# Receptor_RF.net
KiCad netlist of a schematic drawn in EAGLE
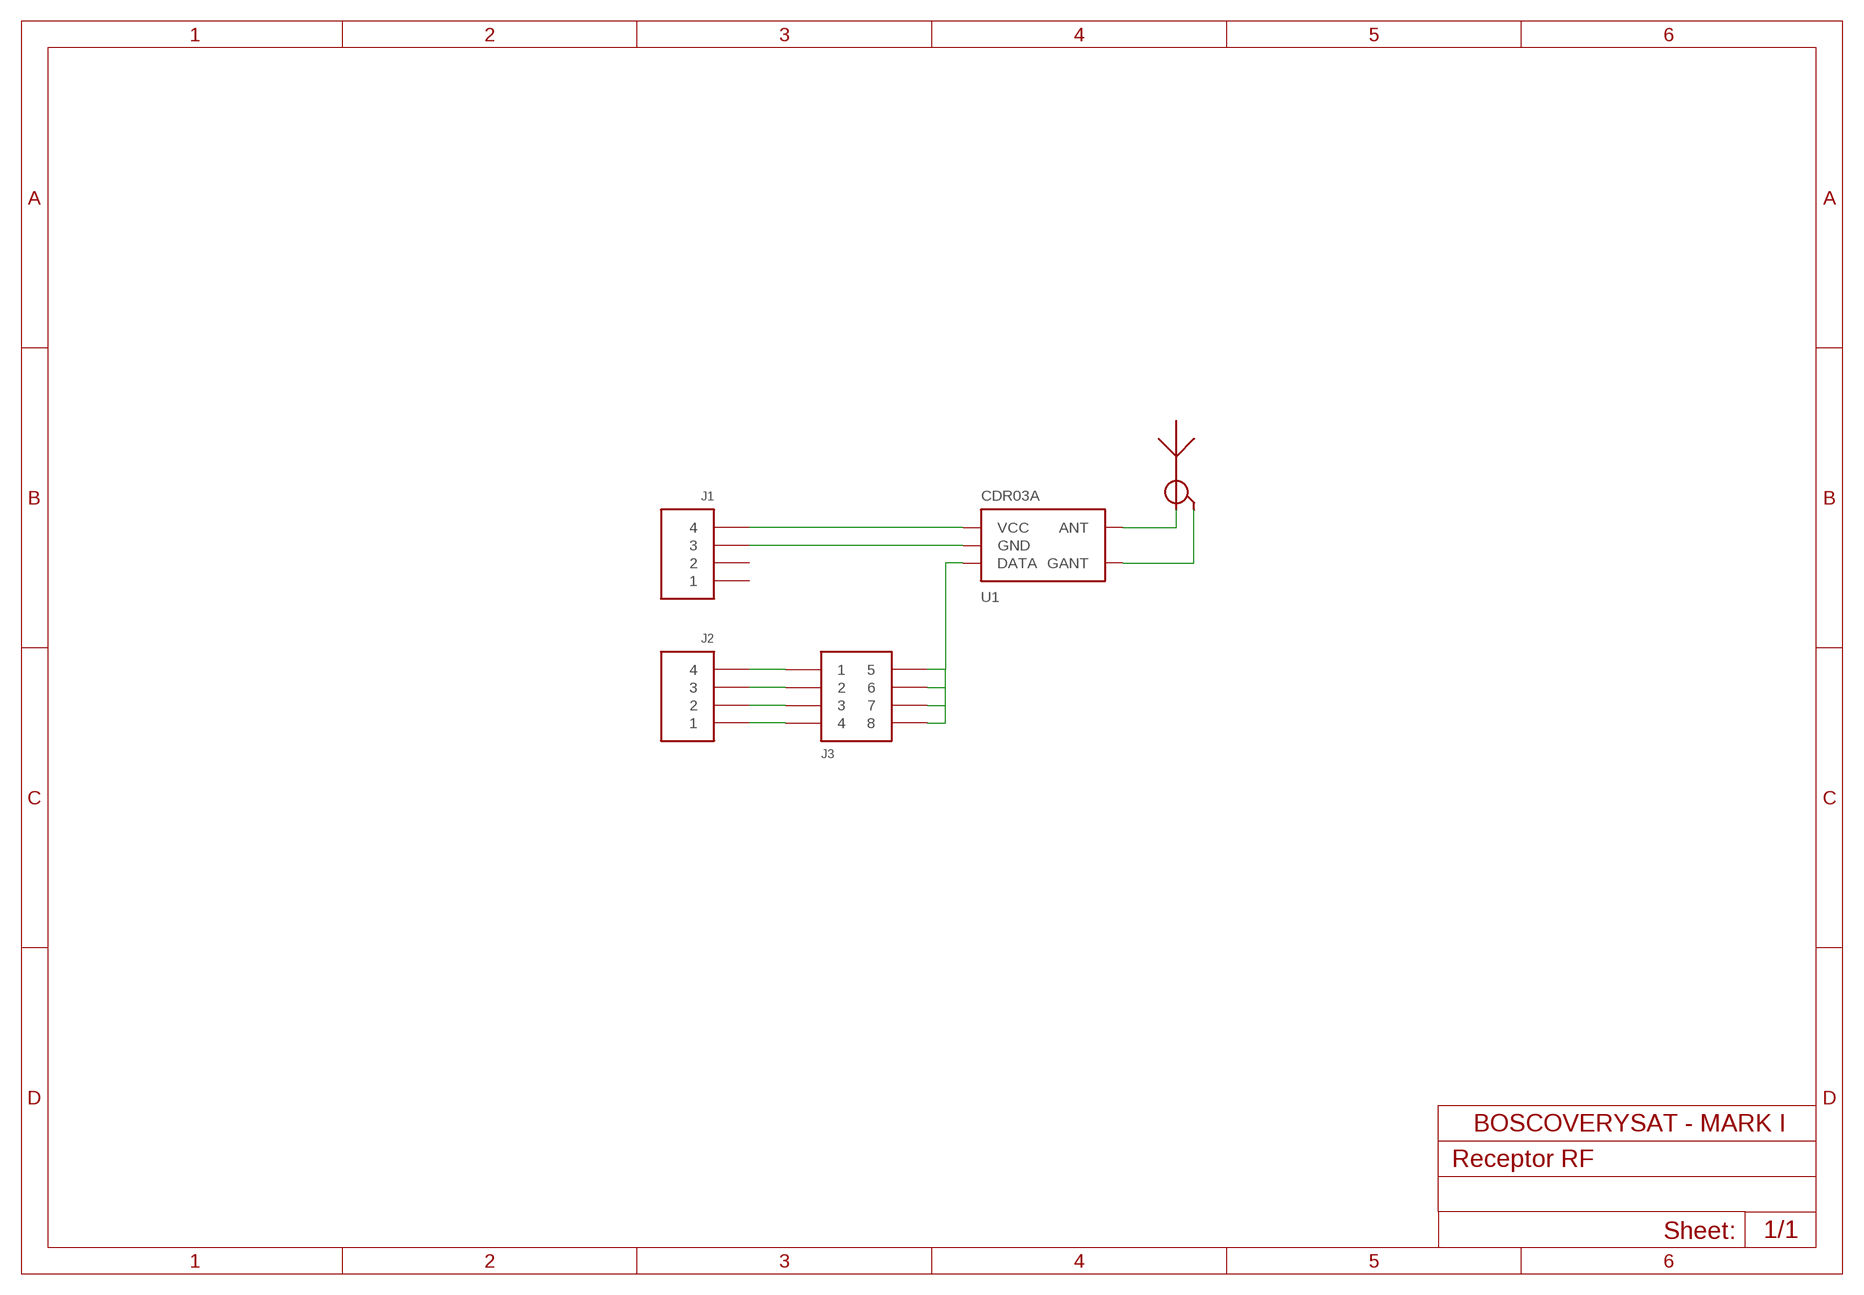
[diagram p0: schematic, sheet 1]

(export (version "E")
  (design (tool "Eeschema 10.0.6"))
  (components
    (comp (ref "J1")
      (value "4-PIN-LINEAR-JUMPER")
      (footprint "eagle-import:4-PIN-LINEAR-JUMPER")
      (libsource (lib "eagle-import") (part "4-PIN-LINEAR-JUMPER"))
    )
    (comp (ref "J2")
      (value "4-PIN-LINEAR-JUMPER")
      (footprint "eagle-import:4-PIN-LINEAR-JUMPER")
      (libsource (lib "eagle-import") (part "4-PIN-LINEAR-JUMPER"))
    )
    (comp (ref "J3")
      (value "8-PIN-JUMPER")
      (footprint "eagle-import:8-PIN-JUMPER")
      (libsource (lib "eagle-import") (part "8-PIN-JUMPER"))
    )
    (comp (ref "U$3")
      (value "ANTENNA")
      (footprint "eagle-import:ANTENNA")
      (libsource (lib "eagle-import") (part "ANTENNA"))
    )
    (comp (ref "U1")
      (value "CDR03A")
      (footprint "eagle-import:CDR03A")
      (libsource (lib "eagle-import") (part "CDR03A"))
    )
  )
  (nets
    (net (code "1") (name "Net-(J1-3)") (class "Default")
      (node (ref "J1") (pin "P$3") (pinfunction "3_P$3") (pintype "bidirectional"))
      (node (ref "U1") (pin "GND") (pinfunction "GND_GND") (pintype "bidirectional"))
    )
    (net (code "2") (name "Net-(J1-4)") (class "Default")
      (node (ref "J1") (pin "P$4") (pinfunction "4_P$4") (pintype "bidirectional"))
      (node (ref "U1") (pin "VCC") (pinfunction "VCC_VCC") (pintype "bidirectional"))
    )
    (net (code "3") (name "Net-(J2-1)") (class "Default")
      (node (ref "J2") (pin "P$1") (pinfunction "1_P$1") (pintype "bidirectional"))
      (node (ref "J3") (pin "P$4") (pinfunction "4_P$4") (pintype "bidirectional"))
    )
    (net (code "4") (name "Net-(J2-2)") (class "Default")
      (node (ref "J2") (pin "P$2") (pinfunction "2_P$2") (pintype "bidirectional"))
      (node (ref "J3") (pin "P$3") (pinfunction "3_P$3") (pintype "bidirectional"))
    )
    (net (code "5") (name "Net-(J2-3)") (class "Default")
      (node (ref "J2") (pin "P$3") (pinfunction "3_P$3") (pintype "bidirectional"))
      (node (ref "J3") (pin "P$2") (pinfunction "2_P$2") (pintype "bidirectional"))
    )
    (net (code "6") (name "Net-(J2-4)") (class "Default")
      (node (ref "J2") (pin "P$4") (pinfunction "4_P$4") (pintype "bidirectional"))
      (node (ref "J3") (pin "P$1") (pinfunction "1_P$1") (pintype "bidirectional"))
    )
    (net (code "7") (name "Net-(J3-5)") (class "Default")
      (node (ref "J3") (pin "P$5") (pinfunction "5_P$5") (pintype "bidirectional"))
      (node (ref "J3") (pin "P$6") (pinfunction "6_P$6") (pintype "bidirectional"))
      (node (ref "J3") (pin "P$7") (pinfunction "7_P$7") (pintype "bidirectional"))
      (node (ref "J3") (pin "P$8") (pinfunction "8_P$8") (pintype "bidirectional"))
      (node (ref "U1") (pin "DATA1") (pinfunction "DATA_DATA1") (pintype "bidirectional"))
      (node (ref "U1") (pin "DATA2") (pinfunction "DATA_DATA2") (pintype "bidirectional"))
    )
    (net (code "8") (name "Net-(U$3-PadANT)") (class "Default")
      (node (ref "U$3") (pin "ANT") (pinfunction "ANT_ANT") (pintype "bidirectional"))
      (node (ref "U1") (pin "ANT") (pinfunction "ANT_ANT") (pintype "output"))
    )
    (net (code "9") (name "Net-(U$3-PadGANT)") (class "Default")
      (node (ref "U$3") (pin "GANT") (pinfunction "GANT_GANT") (pintype "bidirectional"))
      (node (ref "U1") (pin "GANT") (pinfunction "GANT_GANT") (pintype "bidirectional"))
    )
    (net (code "10") (name "unconnected-(J1-1-PadP$1)") (class "Default")
      (node (ref "J1") (pin "P$1") (pinfunction "1_P$1") (pintype "bidirectional"))
    )
    (net (code "11") (name "unconnected-(J1-2-PadP$2)") (class "Default")
      (node (ref "J1") (pin "P$2") (pinfunction "2_P$2") (pintype "bidirectional"))
    )
  )
)
